# Switches1_1.net
KiCad netlist of a schematic drawn in Altium Designer
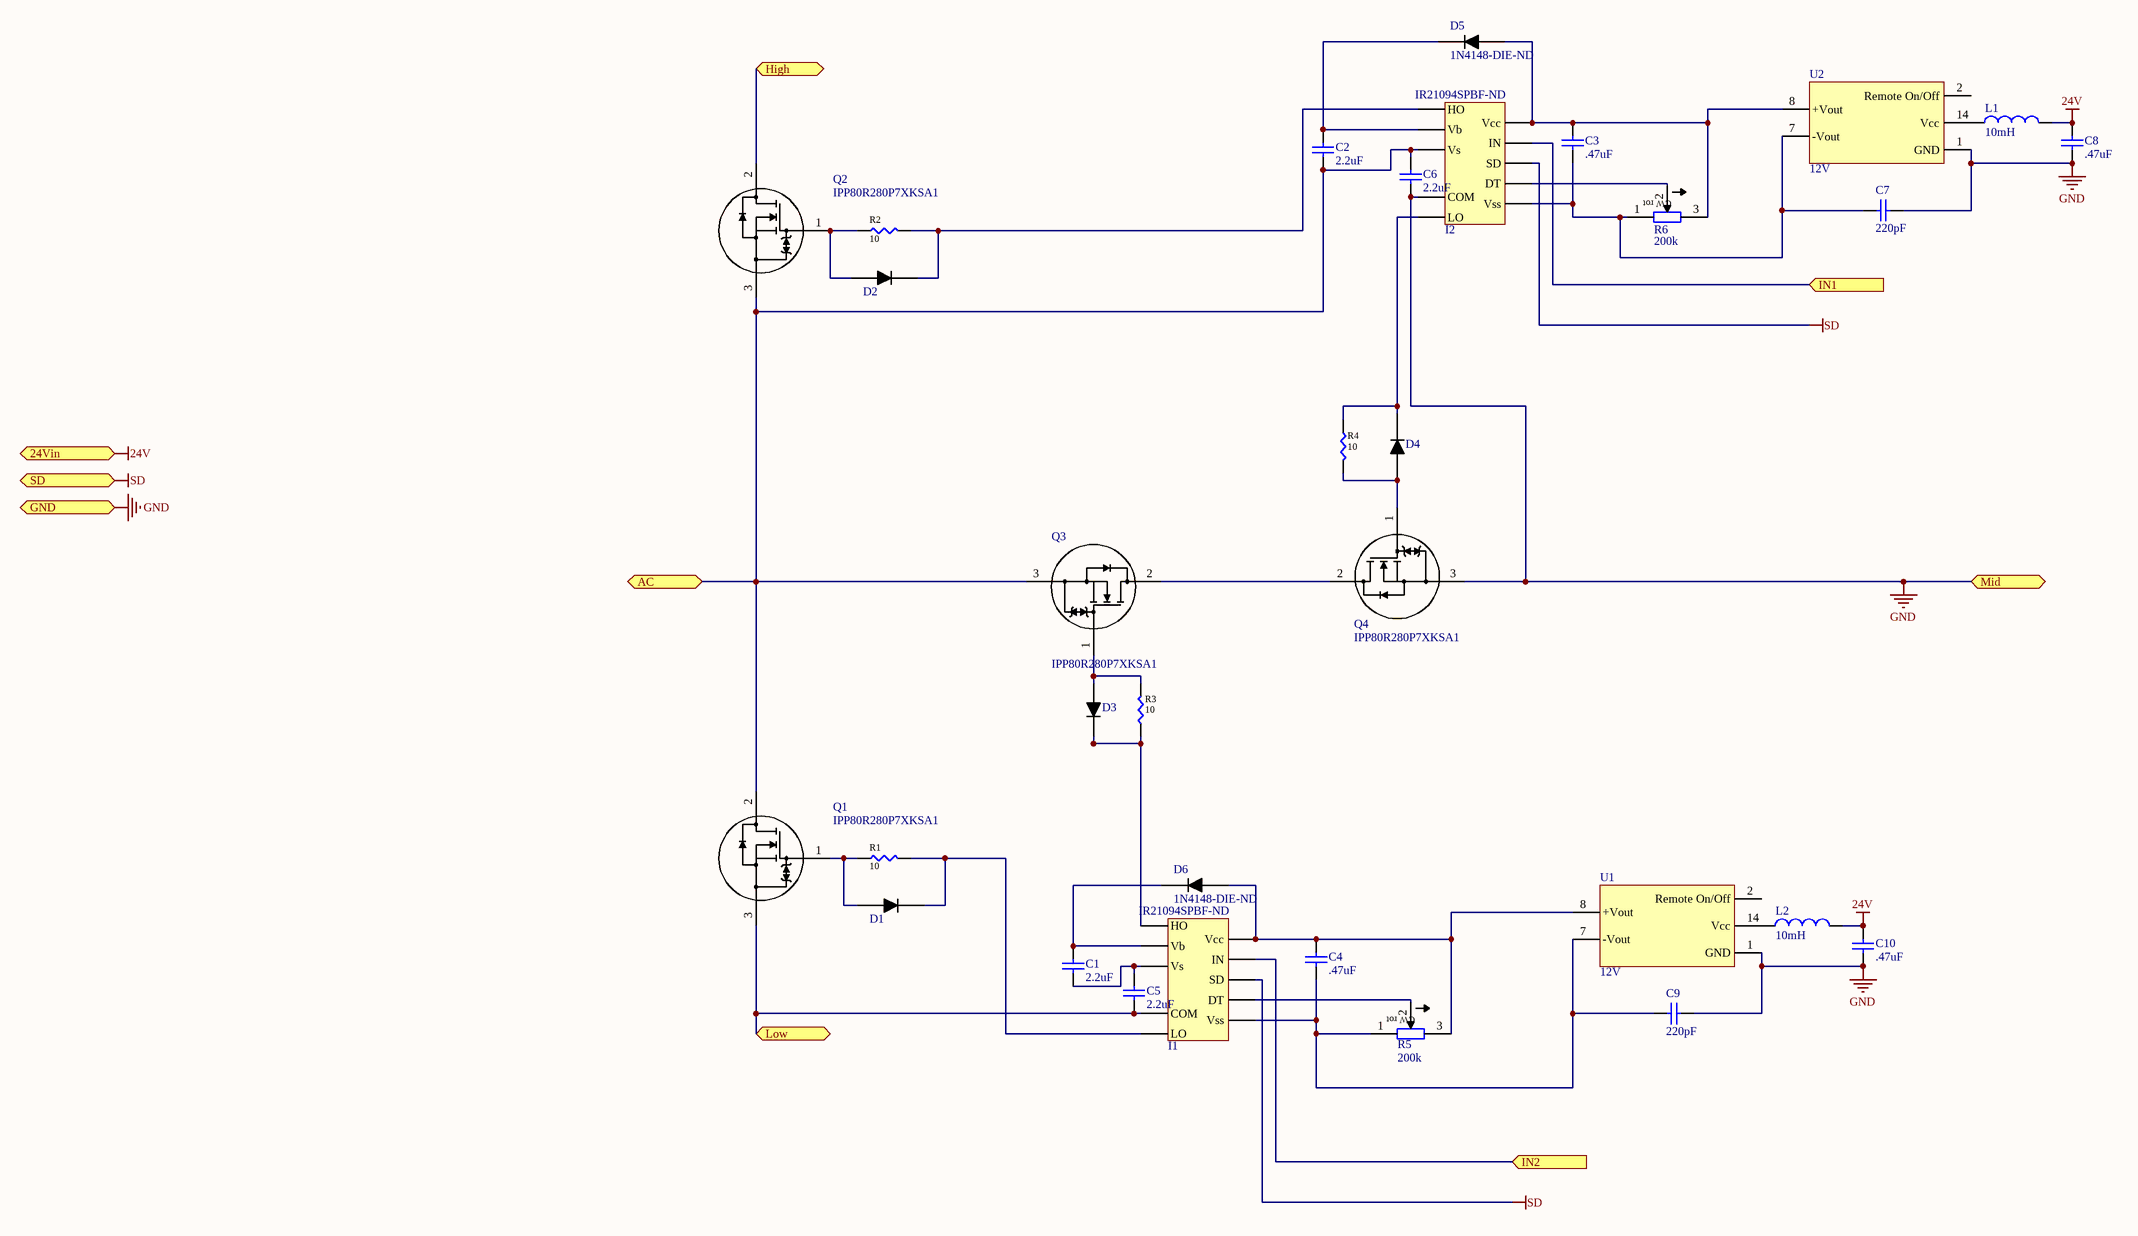
[diagram p0: Switches1.1.SchDoc]

(export (version "E")
  (design (tool "Eeschema 10.0.6"))
  (components
    (comp (ref "C1")
      (value "2.2uF")
      (footprint "RAD-0.3")
      (description "Capacitor")
      (fields (field (name "Comment") "Cap") (field (name "PUBLISHER") "Altium Limited"))
      (libsource (lib "T-Type Converter") (part "Cap"))
    )
    (comp (ref "C2")
      (value "2.2uF")
      (footprint "RAD-0.3")
      (description "Capacitor")
      (fields (field (name "Comment") "Cap") (field (name "PUBLISHER") "Altium Limited"))
      (libsource (lib "T-Type Converter") (part "Cap"))
    )
    (comp (ref "C3")
      (value ".47uF")
      (footprint "RAD-0.3")
      (description "Capacitor")
      (fields (field (name "Comment") "Cap") (field (name "PUBLISHER") "Altium Limited"))
      (libsource (lib "T-Type Converter") (part "Cap"))
    )
    (comp (ref "C4")
      (value ".47uF")
      (footprint "RAD-0.3")
      (description "Capacitor")
      (fields (field (name "Comment") "Cap") (field (name "PUBLISHER") "Altium Limited"))
      (libsource (lib "T-Type Converter") (part "Cap"))
    )
    (comp (ref "C5")
      (value "2.2uF")
      (footprint "RAD-0.3")
      (description "Capacitor")
      (fields (field (name "Comment") "Cap") (field (name "PUBLISHER") "Altium Limited"))
      (libsource (lib "T-Type Converter") (part "Cap"))
    )
    (comp (ref "C6")
      (value "2.2uF")
      (footprint "RAD-0.3")
      (description "Capacitor")
      (fields (field (name "Comment") "Cap") (field (name "PUBLISHER") "Altium Limited"))
      (libsource (lib "T-Type Converter") (part "Cap"))
    )
    (comp (ref "C7")
      (value "220pF")
      (footprint "RAD-0.3")
      (description "Capacitor")
      (fields (field (name "Comment") "Cap") (field (name "PUBLISHER") "Altium Limited"))
      (libsource (lib "T-Type Converter") (part "Cap"))
    )
    (comp (ref "C8")
      (value ".47uF")
      (footprint "RAD-0.3")
      (description "Capacitor")
      (fields (field (name "Comment") "Cap") (field (name "PUBLISHER") "Altium Limited"))
      (libsource (lib "T-Type Converter") (part "Cap"))
    )
    (comp (ref "C9")
      (value "220pF")
      (footprint "RAD-0.3")
      (description "Capacitor")
      (fields (field (name "Comment") "Cap") (field (name "PUBLISHER") "Altium Limited"))
      (libsource (lib "T-Type Converter") (part "Cap"))
    )
    (comp (ref "C10")
      (value ".47uF")
      (footprint "RAD-0.3")
      (description "Capacitor")
      (fields (field (name "Comment") "Cap") (field (name "PUBLISHER") "Altium Limited"))
      (libsource (lib "T-Type Converter") (part "Cap"))
    )
    (comp (ref "D1")
      (value "1N4148")
      (footprint "Diode 1n4148")
      (description "Diode")
      (fields (field (name "MANUFACTURER") "Fairchild Semiconductor"))
      (libsource (lib "T-Type Converter") (part "1N4148"))
    )
    (comp (ref "D2")
      (value "1N4148")
      (footprint "Diode 1n4148")
      (description "Diode")
      (fields (field (name "MANUFACTURER") "Fairchild Semiconductor"))
      (libsource (lib "T-Type Converter") (part "1N4148"))
    )
    (comp (ref "D3")
      (value "1N4148")
      (footprint "DO-35_02")
      (description "Diode")
      (fields (field (name "MANUFACTURER") "Fairchild Semiconductor"))
      (libsource (lib "T-Type Converter") (part "1N4148"))
    )
    (comp (ref "D4")
      (value "1N4148")
      (footprint "DO-35_02")
      (description "Diode")
      (fields (field (name "MANUFACTURER") "Fairchild Semiconductor"))
      (libsource (lib "T-Type Converter") (part "1N4148"))
    )
    (comp (ref "D5")
      (value "1N4148")
      (footprint "DO-35_02")
      (description "Diode")
      (fields
        (field (name "MANUFACTURER") "Fairchild Semiconductor")
        (field (name "SUPPLIER PART NUMBER 1") "1N4148-DIE-ND")
      )
      (libsource (lib "T-Type Converter") (part "1N4148"))
    )
    (comp (ref "D6")
      (value "1N4148")
      (footprint "DO-35_02")
      (description "Diode")
      (fields
        (field (name "MANUFACTURER") "Fairchild Semiconductor")
        (field (name "SUPPLIER PART NUMBER 1") "1N4148-DIE-ND")
      )
      (libsource (lib "T-Type Converter") (part "1N4148"))
    )
    (comp (ref "I1")
      (value "IR21094")
      (footprint "DIP14")
      (description "HALF-BRIDGE DRIVER")
      (fields
        (field (name "SUPPLIER PART NUMBER 1") "IR21094SPBF-ND")
        (field (name "MANUFACTURER") "International Rectifier")
        (field (name "MANUFACTURER PART NUMBER") "IR21094SPBF")
      )
      (libsource (lib "T-Type Converter") (part "IR21094"))
    )
    (comp (ref "I2")
      (value "IR21094")
      (footprint "DIP14")
      (description "HALF-BRIDGE DRIVER")
      (fields
        (field (name "SUPPLIER PART NUMBER 1") "IR21094SPBF-ND")
        (field (name "MANUFACTURER") "International Rectifier")
        (field (name "MANUFACTURER PART NUMBER") "IR21094SPBF")
      )
      (libsource (lib "T-Type Converter") (part "IR21094"))
    )
    (comp (ref "L1")
      (value "10mH")
      (footprint "TCK-047")
      (description "Inductor")
      (fields (field (name "PUBLISHER") "Altium Limited"))
      (libsource (lib "Miscellaneous Devices") (part "Inductor"))
    )
    (comp (ref "L2")
      (value "10mH")
      (footprint "TCK-047")
      (description "Inductor")
      (fields (field (name "PUBLISHER") "Altium Limited"))
      (libsource (lib "Miscellaneous Devices") (part "Inductor"))
    )
    (comp (ref "Q1")
      (value "IPP80R280P7XKSA1")
      (footprint "IPP65R110CFD")
      (description "MOSFET")
      (fields (field (name "MANUFACTURER") "Infineon"))
      (libsource (lib "") (part "IPP80R280P7XKSA1_1"))
    )
    (comp (ref "Q2")
      (value "IPP80R280P7XKSA1")
      (footprint "IPP65R110CFD")
      (description "MOSFET")
      (fields (field (name "MANUFACTURER") "Infineon"))
      (libsource (lib "") (part "IPP80R280P7XKSA1_1"))
    )
    (comp (ref "Q3")
      (value "IPP80R280P7XKSA1")
      (footprint "IPP65R110CFD")
      (description "MOSFET")
      (fields (field (name "MANUFACTURER") "Infineon"))
      (libsource (lib "T-Type Converter") (part "IPP80R280P7XKSA1"))
    )
    (comp (ref "Q4")
      (value "IPP80R280P7XKSA1")
      (footprint "IPP65R110CFD")
      (fields (field (name "MANUFACTURER") "Infineon"))
      (libsource (lib "") (part "IPP80R280P7XKSA1_2"))
    )
    (comp (ref "R1")
      (value "10")
      (footprint "R_1206")
      (description "RES SMD 1% 1/4W 1206")
      (fields
        (field (name "MANUFACTURER") "Panasonic Electronic Components")
        (field (name "MANUFACTURER PART NUMBER") "ERJ-8ENF9101V")
      )
      (libsource (lib "T-Type Converter") (part "RES_SMD1"))
    )
    (comp (ref "R2")
      (value "10")
      (footprint "R_1206")
      (description "RES SMD 1% 1/4W 1206")
      (fields
        (field (name "MANUFACTURER") "Panasonic Electronic Components")
        (field (name "MANUFACTURER PART NUMBER") "ERJ-8ENF9101V")
      )
      (libsource (lib "T-Type Converter") (part "RES_SMD1"))
    )
    (comp (ref "R3")
      (value "10")
      (footprint "R_1206")
      (description "RES SMD 1% 1/4W 1206")
      (fields
        (field (name "MANUFACTURER") "Panasonic Electronic Components")
        (field (name "MANUFACTURER PART NUMBER") "ERJ-8ENF9101V")
      )
      (libsource (lib "T-Type Converter") (part "RES_SMD1"))
    )
    (comp (ref "R4")
      (value "10")
      (footprint "R_1206")
      (description "RES SMD 1% 1/4W 1206")
      (fields
        (field (name "MANUFACTURER") "Panasonic Electronic Components")
        (field (name "MANUFACTURER PART NUMBER") "ERJ-8ENF9101V")
      )
      (libsource (lib "T-Type Converter") (part "RES_SMD1"))
    )
    (comp (ref "R5")
      (value "200k")
      (footprint "AXIAL-0.6")
      (description "Variable Resistor")
      (fields
        (field (name "MANUFACTURER") "Nidec Copal")
        (field (name "MANUFACTURER PART NUMBER") "CT-6EP103")
        (field (name "PUBLISHER") "Altium Limited")
      )
      (libsource (lib "T-Type Converter") (part "Res Adj2"))
    )
    (comp (ref "R6")
      (value "200k")
      (footprint "AXIAL-0.6")
      (description "Variable Resistor")
      (fields
        (field (name "MANUFACTURER") "Nidec Copal")
        (field (name "MANUFACTURER PART NUMBER") "CT-6EP103")
        (field (name "PUBLISHER") "Altium Limited")
      )
      (libsource (lib "T-Type Converter") (part "Res Adj2"))
    )
    (comp (ref "U1")
      (value "12V")
      (footprint "PID DC-DC Converter - duplicate")
      (description "12V DC-DC Converter")
      (fields
        (field (name "MANUFACTURER") "Traco Power")
        (field (name "MANUFACTURER PART NUMBER") "TDR3-2412")
      )
      (libsource (lib "T-Type Converter") (part "TDR 3-2412"))
    )
    (comp (ref "U2")
      (value "12V")
      (footprint "PID DC-DC Converter - duplicate")
      (description "12V DC-DC Converter")
      (fields
        (field (name "MANUFACTURER") "Traco Power")
        (field (name "MANUFACTURER PART NUMBER") "TDR3-2412")
      )
      (libsource (lib "T-Type Converter") (part "TDR 3-2412"))
    )
  )
  (nets
    (net (code "1") (name "/AC") (class "Default")
      (node (ref "C2") (pin "1") (pinfunction "1_1") (pintype "passive"))
      (node (ref "C6") (pin "2") (pinfunction "2_2") (pintype "passive"))
      (node (ref "I2") (pin "8") (pinfunction "Vs_8") (pintype "passive"))
      (node (ref "Q1") (pin "2") (pinfunction "Drain_2") (pintype "passive"))
      (node (ref "Q2") (pin "3") (pinfunction "Source_3") (pintype "passive"))
      (node (ref "Q3") (pin "3") (pinfunction "Source_3") (pintype "passive"))
    )
    (net (code "2") (name "/High") (class "Default")
      (node (ref "Q2") (pin "2") (pinfunction "Drain_2") (pintype "passive"))
    )
    (net (code "3") (name "/IN1") (class "Default")
      (node (ref "I2") (pin "2") (pinfunction "IN_2") (pintype "passive"))
    )
    (net (code "4") (name "/IN2") (class "Default")
      (node (ref "I1") (pin "2") (pinfunction "IN_2") (pintype "passive"))
    )
    (net (code "5") (name "/Low") (class "Default")
      (node (ref "C5") (pin "1") (pinfunction "1_1") (pintype "passive"))
      (node (ref "I1") (pin "6") (pinfunction "COM_6") (pintype "passive"))
      (node (ref "Q1") (pin "3") (pinfunction "Source_3") (pintype "passive"))
    )
    (net (code "6") (name "24V") (class "Default")
      (node (ref "C10") (pin "2") (pinfunction "2_2") (pintype "passive"))
      (node (ref "C8") (pin "2") (pinfunction "2_2") (pintype "passive"))
      (node (ref "L1") (pin "1") (pinfunction "1_1") (pintype "passive"))
      (node (ref "L2") (pin "1") (pinfunction "1_1") (pintype "passive"))
    )
    (net (code "7") (name "GND") (class "Default")
      (node (ref "C10") (pin "1") (pinfunction "1_1") (pintype "passive"))
      (node (ref "C6") (pin "1") (pinfunction "1_1") (pintype "passive"))
      (node (ref "C7") (pin "2") (pinfunction "2_2") (pintype "passive"))
      (node (ref "C8") (pin "1") (pinfunction "1_1") (pintype "passive"))
      (node (ref "C9") (pin "2") (pinfunction "2_2") (pintype "passive"))
      (node (ref "I2") (pin "6") (pinfunction "COM_6") (pintype "passive"))
      (node (ref "Q4") (pin "3") (pinfunction "Source_3") (pintype "passive"))
      (node (ref "U1") (pin "1") (pinfunction "GND_1") (pintype "power_in"))
      (node (ref "U2") (pin "1") (pinfunction "GND_1") (pintype "power_in"))
    )
    (net (code "8") (name "Net-(D1-Anode)") (class "Default")
      (node (ref "D1") (pin "2") (pinfunction "Anode_2") (pintype "passive"))
      (node (ref "Q1") (pin "1") (pinfunction "Gate_1") (pintype "passive"))
      (node (ref "R1") (pin "2") (pinfunction "2_2") (pintype "passive"))
    )
    (net (code "9") (name "Net-(D1-Cathode)") (class "Default")
      (node (ref "D1") (pin "1") (pinfunction "Cathode_1") (pintype "passive"))
      (node (ref "I1") (pin "7") (pinfunction "LO_7") (pintype "passive"))
      (node (ref "R1") (pin "1") (pinfunction "1_1") (pintype "passive"))
    )
    (net (code "10") (name "Net-(D2-Anode)") (class "Default")
      (node (ref "D2") (pin "2") (pinfunction "Anode_2") (pintype "passive"))
      (node (ref "Q2") (pin "1") (pinfunction "Gate_1") (pintype "passive"))
      (node (ref "R2") (pin "2") (pinfunction "2_2") (pintype "passive"))
    )
    (net (code "11") (name "Net-(D2-Cathode)") (class "Default")
      (node (ref "D2") (pin "1") (pinfunction "Cathode_1") (pintype "passive"))
      (node (ref "I2") (pin "12") (pinfunction "HO_12") (pintype "passive"))
      (node (ref "R2") (pin "1") (pinfunction "1_1") (pintype "passive"))
    )
    (net (code "12") (name "Net-(D3-Anode)") (class "Default")
      (node (ref "D3") (pin "2") (pinfunction "Anode_2") (pintype "passive"))
      (node (ref "Q3") (pin "1") (pinfunction "Gate_1") (pintype "passive"))
      (node (ref "R3") (pin "1") (pinfunction "1_1") (pintype "passive"))
    )
    (net (code "13") (name "Net-(D3-Cathode)") (class "Default")
      (node (ref "D3") (pin "1") (pinfunction "Cathode_1") (pintype "passive"))
      (node (ref "I1") (pin "12") (pinfunction "HO_12") (pintype "passive"))
      (node (ref "R3") (pin "2") (pinfunction "2_2") (pintype "passive"))
    )
    (net (code "14") (name "Net-(D4-Anode)") (class "Default")
      (node (ref "D4") (pin "2") (pinfunction "Anode_2") (pintype "passive"))
      (node (ref "Q4") (pin "1") (pinfunction "Gate_1") (pintype "passive"))
      (node (ref "R4") (pin "1") (pinfunction "1_1") (pintype "passive"))
    )
    (net (code "15") (name "Net-(D4-Cathode)") (class "Default")
      (node (ref "D4") (pin "1") (pinfunction "Cathode_1") (pintype "passive"))
      (node (ref "I2") (pin "7") (pinfunction "LO_7") (pintype "passive"))
      (node (ref "R4") (pin "2") (pinfunction "2_2") (pintype "passive"))
    )
    (net (code "16") (name "Net-(D5-Anode)") (class "Default")
      (node (ref "C3") (pin "2") (pinfunction "2_2") (pintype "passive"))
      (node (ref "D5") (pin "2") (pinfunction "Anode_2") (pintype "passive"))
      (node (ref "I2") (pin "1") (pinfunction "Vcc_1") (pintype "passive"))
      (node (ref "R6") (pin "3") (pintype "passive"))
      (node (ref "U2") (pin "8") (pinfunction "+Vout_8") (pintype "passive"))
    )
    (net (code "17") (name "Net-(D5-Cathode)") (class "Default")
      (node (ref "C2") (pin "2") (pinfunction "2_2") (pintype "passive"))
      (node (ref "D5") (pin "1") (pinfunction "Cathode_1") (pintype "passive"))
      (node (ref "I2") (pin "13") (pinfunction "Vb_13") (pintype "passive"))
    )
    (net (code "18") (name "Net-(D6-Anode)") (class "Default")
      (node (ref "C4") (pin "2") (pinfunction "2_2") (pintype "passive"))
      (node (ref "D6") (pin "2") (pinfunction "Anode_2") (pintype "passive"))
      (node (ref "I1") (pin "1") (pinfunction "Vcc_1") (pintype "passive"))
      (node (ref "R5") (pin "3") (pintype "passive"))
      (node (ref "U1") (pin "8") (pinfunction "+Vout_8") (pintype "passive"))
    )
    (net (code "19") (name "Net-(D6-Cathode)") (class "Default")
      (node (ref "C1") (pin "2") (pinfunction "2_2") (pintype "passive"))
      (node (ref "D6") (pin "1") (pinfunction "Cathode_1") (pintype "passive"))
      (node (ref "I1") (pin "13") (pinfunction "Vb_13") (pintype "passive"))
    )
    (net (code "20") (name "Net-(I1-DT)") (class "Default")
      (node (ref "I1") (pin "4") (pinfunction "DT_4") (pintype "passive"))
      (node (ref "R5") (pin "2") (pinfunction "3_2") (pintype "passive"))
    )
    (net (code "21") (name "Net-(I1-Vs)") (class "Default")
      (node (ref "C1") (pin "1") (pinfunction "1_1") (pintype "passive"))
      (node (ref "C5") (pin "2") (pinfunction "2_2") (pintype "passive"))
      (node (ref "I1") (pin "8") (pinfunction "Vs_8") (pintype "passive"))
    )
    (net (code "22") (name "Net-(I1-Vss)") (class "Default")
      (node (ref "C4") (pin "1") (pinfunction "1_1") (pintype "passive"))
      (node (ref "C9") (pin "1") (pinfunction "1_1") (pintype "passive"))
      (node (ref "I1") (pin "5") (pinfunction "Vss_5") (pintype "passive"))
      (node (ref "R5") (pin "1") (pintype "passive"))
      (node (ref "U1") (pin "7") (pinfunction "-Vout_7") (pintype "passive"))
    )
    (net (code "23") (name "Net-(I2-DT)") (class "Default")
      (node (ref "I2") (pin "4") (pinfunction "DT_4") (pintype "passive"))
      (node (ref "R6") (pin "2") (pinfunction "3_2") (pintype "passive"))
    )
    (net (code "24") (name "Net-(I2-Vss)") (class "Default")
      (node (ref "C3") (pin "1") (pinfunction "1_1") (pintype "passive"))
      (node (ref "C7") (pin "1") (pinfunction "1_1") (pintype "passive"))
      (node (ref "I2") (pin "5") (pinfunction "Vss_5") (pintype "passive"))
      (node (ref "R6") (pin "1") (pintype "passive"))
      (node (ref "U2") (pin "7") (pinfunction "-Vout_7") (pintype "passive"))
    )
    (net (code "25") (name "Net-(Q3-Drain)") (class "Default")
      (node (ref "Q3") (pin "2") (pinfunction "Drain_2") (pintype "passive"))
      (node (ref "Q4") (pin "2") (pinfunction "Drain_2") (pintype "passive"))
    )
    (net (code "26") (name "Net-(U1-Vcc)") (class "Default")
      (node (ref "L2") (pin "2") (pinfunction "2_2") (pintype "passive"))
      (node (ref "U1") (pin "14") (pinfunction "Vcc_14") (pintype "passive"))
    )
    (net (code "27") (name "Net-(U2-Vcc)") (class "Default")
      (node (ref "L1") (pin "2") (pinfunction "2_2") (pintype "passive"))
      (node (ref "U2") (pin "14") (pinfunction "Vcc_14") (pintype "passive"))
    )
    (net (code "28") (name "SD") (class "Default")
      (node (ref "I1") (pin "3") (pinfunction "SD_3") (pintype "passive"))
      (node (ref "I2") (pin "3") (pinfunction "SD_3") (pintype "passive"))
    )
    (net (code "29") (name "unconnected-(U1-Remote_On{slash}Off-Pad2)") (class "Default")
      (node (ref "U1") (pin "2") (pinfunction "Remote_On/Off_2") (pintype "passive"))
    )
    (net (code "30") (name "unconnected-(U2-Remote_On{slash}Off-Pad2)") (class "Default")
      (node (ref "U2") (pin "2") (pinfunction "Remote_On/Off_2") (pintype "passive"))
    )
  )
)
